# transfo_schematic.net
KiCad netlist of a schematic drawn in EAGLE
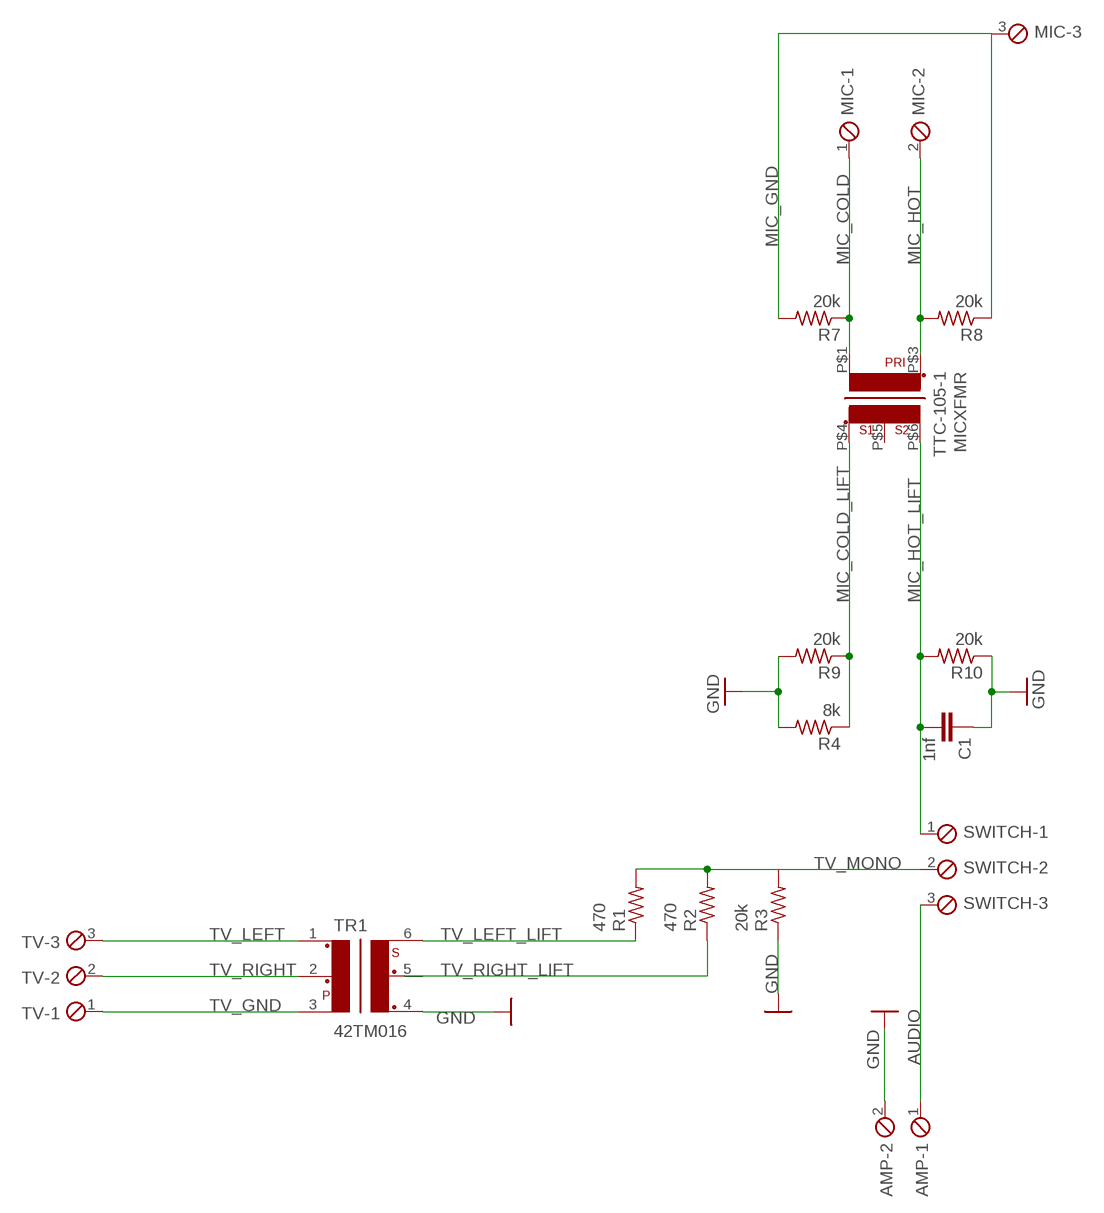
[diagram p0: schematic, sheet 1]

(export (version "E")
  (design (tool "Eeschema 10.0.6"))
  (components
    (comp (ref "AMP")
      (value "TB3POL")
      (footprint "eagle-import:2POL381")
      (libsource (lib "eagle-import") (part "MKDS1/2-3,81"))
    )
    (comp (ref "C1")
      (value "1nf")
      (footprint "eagle-import:CAP-PTH-SMALL-KIT")
      (libsource (lib "eagle-import") (part "0.1UF-KIT-EZ-50V-20%"))
    )
    (comp (ref "MIC")
      (value "TB3POL")
      (footprint "eagle-import:3POL381")
      (libsource (lib "eagle-import") (part "MKDS1/3-3,81"))
    )
    (comp (ref "MICXFMR")
      (value "TTC-105-1")
      (footprint "eagle-import:TAMURA-TTC-105-1")
      (libsource (lib "eagle-import") (part "TAMURA-TTC-105-1"))
    )
    (comp (ref "R1")
      (value "470")
      (footprint "eagle-import:0204_7")
      (libsource (lib "eagle-import") (part "R-US_0204/7"))
    )
    (comp (ref "R2")
      (value "470")
      (footprint "eagle-import:0204_7")
      (libsource (lib "eagle-import") (part "R-US_0204/7"))
    )
    (comp (ref "R3")
      (value "20k")
      (footprint "eagle-import:0204_7")
      (libsource (lib "eagle-import") (part "R-US_0204/7"))
    )
    (comp (ref "R4")
      (value "8k")
      (footprint "eagle-import:0204_7")
      (libsource (lib "eagle-import") (part "R-US_0204/7"))
    )
    (comp (ref "R7")
      (value "20k")
      (footprint "eagle-import:0204_7")
      (libsource (lib "eagle-import") (part "R-US_0204/7"))
    )
    (comp (ref "R8")
      (value "20k")
      (footprint "eagle-import:0204_7")
      (libsource (lib "eagle-import") (part "R-US_0204/7"))
    )
    (comp (ref "R9")
      (value "20k")
      (footprint "eagle-import:0204_7")
      (libsource (lib "eagle-import") (part "R-US_0204/7"))
    )
    (comp (ref "R10")
      (value "20k")
      (footprint "eagle-import:0204_7")
      (libsource (lib "eagle-import") (part "R-US_0204/7"))
    )
    (comp (ref "SWITCH")
      (value "TB3POL")
      (footprint "eagle-import:3POL381")
      (libsource (lib "eagle-import") (part "MKDS1/3-3,81"))
    )
    (comp (ref "TR1")
      (value "42TM016")
      (footprint "eagle-import:42TM")
      (libsource (lib "eagle-import") (part "42T?M016"))
    )
    (comp (ref "TV")
      (value "TB3POL")
      (footprint "eagle-import:3POL381")
      (libsource (lib "eagle-import") (part "MKDS1/3-3,81"))
    )
  )
  (nets
    (net (code "1") (name "/AUDIO") (class "Default")
      (node (ref "AMP") (pin "1") (pinfunction "1_1") (pintype "passive"))
      (node (ref "SWITCH") (pin "3") (pinfunction "1_3") (pintype "passive"))
    )
    (net (code "2") (name "/MIC_COLD") (class "Default")
      (node (ref "MIC") (pin "1") (pinfunction "1_1") (pintype "passive"))
      (node (ref "MICXFMR") (pin "P$1") (pinfunction "1_P$1") (pintype "passive"))
      (node (ref "R7") (pin "1") (pinfunction "1_1") (pintype "passive"))
    )
    (net (code "3") (name "/MIC_COLD_LIFT") (class "Default")
      (node (ref "MICXFMR") (pin "P$4") (pinfunction "4_P$4") (pintype "passive"))
      (node (ref "R4") (pin "1") (pinfunction "1_1") (pintype "passive"))
      (node (ref "R9") (pin "1") (pinfunction "1_1") (pintype "passive"))
    )
    (net (code "4") (name "/MIC_GND") (class "Default")
      (node (ref "MIC") (pin "3") (pinfunction "1_3") (pintype "passive"))
      (node (ref "R7") (pin "2") (pinfunction "2_2") (pintype "passive"))
      (node (ref "R8") (pin "1") (pinfunction "1_1") (pintype "passive"))
    )
    (net (code "5") (name "/MIC_HOT") (class "Default")
      (node (ref "MIC") (pin "2") (pinfunction "1_2") (pintype "passive"))
      (node (ref "MICXFMR") (pin "P$3") (pinfunction "3_P$3") (pintype "passive"))
      (node (ref "R8") (pin "2") (pinfunction "2_2") (pintype "passive"))
    )
    (net (code "6") (name "/MIC_HOT_LIFT") (class "Default")
      (node (ref "C1") (pin "2") (pinfunction "2_2") (pintype "passive"))
      (node (ref "MICXFMR") (pin "P$6") (pinfunction "6_P$6") (pintype "passive"))
      (node (ref "R10") (pin "2") (pinfunction "2_2") (pintype "passive"))
      (node (ref "SWITCH") (pin "1") (pinfunction "1_1") (pintype "passive"))
    )
    (net (code "7") (name "/TV_GND") (class "Default")
      (node (ref "TR1") (pin "3") (pinfunction "3_3") (pintype "passive"))
      (node (ref "TV") (pin "1") (pinfunction "1_1") (pintype "passive"))
    )
    (net (code "8") (name "/TV_LEFT") (class "Default")
      (node (ref "TR1") (pin "1") (pinfunction "1_1") (pintype "passive"))
      (node (ref "TV") (pin "3") (pinfunction "1_3") (pintype "passive"))
    )
    (net (code "9") (name "/TV_LEFT_LIFT") (class "Default")
      (node (ref "R1") (pin "1") (pinfunction "1_1") (pintype "passive"))
      (node (ref "TR1") (pin "6") (pinfunction "6_6") (pintype "passive"))
    )
    (net (code "10") (name "/TV_MONO") (class "Default")
      (node (ref "R1") (pin "2") (pinfunction "2_2") (pintype "passive"))
      (node (ref "R2") (pin "2") (pinfunction "2_2") (pintype "passive"))
      (node (ref "R3") (pin "2") (pinfunction "2_2") (pintype "passive"))
      (node (ref "SWITCH") (pin "2") (pinfunction "1_2") (pintype "passive"))
    )
    (net (code "11") (name "/TV_RIGHT") (class "Default")
      (node (ref "TR1") (pin "2") (pinfunction "2_2") (pintype "passive"))
      (node (ref "TV") (pin "2") (pinfunction "1_2") (pintype "passive"))
    )
    (net (code "12") (name "/TV_RIGHT_LIFT") (class "Default")
      (node (ref "R2") (pin "1") (pinfunction "1_1") (pintype "passive"))
      (node (ref "TR1") (pin "5") (pinfunction "5_5") (pintype "passive"))
    )
    (net (code "13") (name "GND") (class "Default")
      (node (ref "AMP") (pin "2") (pinfunction "1_2") (pintype "passive"))
      (node (ref "C1") (pin "1") (pinfunction "1_1") (pintype "passive"))
      (node (ref "R10") (pin "1") (pinfunction "1_1") (pintype "passive"))
      (node (ref "R3") (pin "1") (pinfunction "1_1") (pintype "passive"))
      (node (ref "R4") (pin "2") (pinfunction "2_2") (pintype "passive"))
      (node (ref "R9") (pin "2") (pinfunction "2_2") (pintype "passive"))
      (node (ref "TR1") (pin "4") (pinfunction "4_4") (pintype "passive"))
    )
    (net (code "14") (name "unconnected-(MICXFMR-5-PadP$5)") (class "Default")
      (node (ref "MICXFMR") (pin "P$5") (pinfunction "5_P$5") (pintype "passive"))
    )
  )
)
